# TopLevel.net
KiCad netlist of a schematic drawn in Altium Designer
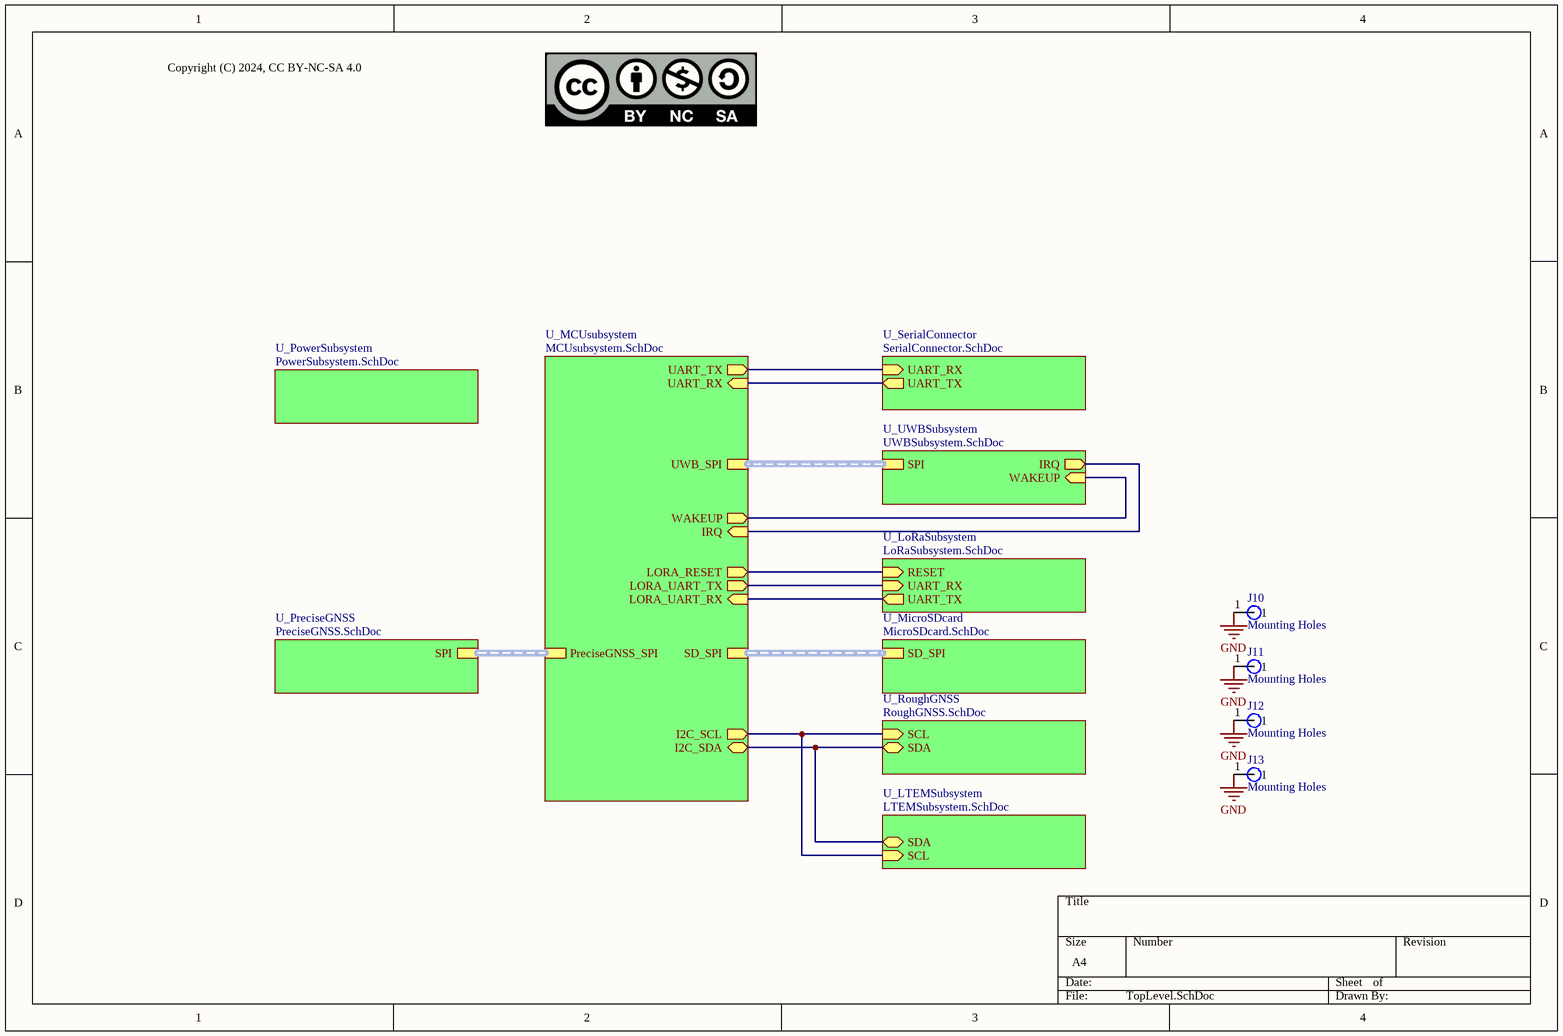
[diagram p0: TopLevel.SchDoc]

(export (version "E")
  (design (tool "Eeschema 10.0.6"))
  (components
    (comp (ref "J10")
      (value "Mounting Holes")
      (footprint "Mounting Hole")
      (libsource (lib "Hole") (part "Mounting Holes"))
    )
    (comp (ref "J11")
      (value "Mounting Holes")
      (footprint "Mounting Hole")
      (libsource (lib "Hole") (part "Mounting Holes"))
    )
    (comp (ref "J12")
      (value "Mounting Holes")
      (footprint "Mounting Hole")
      (libsource (lib "Hole") (part "Mounting Holes"))
    )
    (comp (ref "J13")
      (value "Mounting Holes")
      (footprint "Mounting Hole")
      (libsource (lib "Hole") (part "Mounting Holes"))
    )
  )
  (nets
    (net (code "13") (name "GND") (class "Default")
      (node (ref "J10") (pin "1") (pinfunction "1_1") (pintype "passive"))
      (node (ref "J11") (pin "1") (pinfunction "1_1") (pintype "passive"))
      (node (ref "J12") (pin "1") (pinfunction "1_1") (pintype "passive"))
      (node (ref "J13") (pin "1") (pinfunction "1_1") (pintype "passive"))
    )
  )
)
